# eeZeeAmp.net
KiCad netlist of a schematic drawn in EAGLE
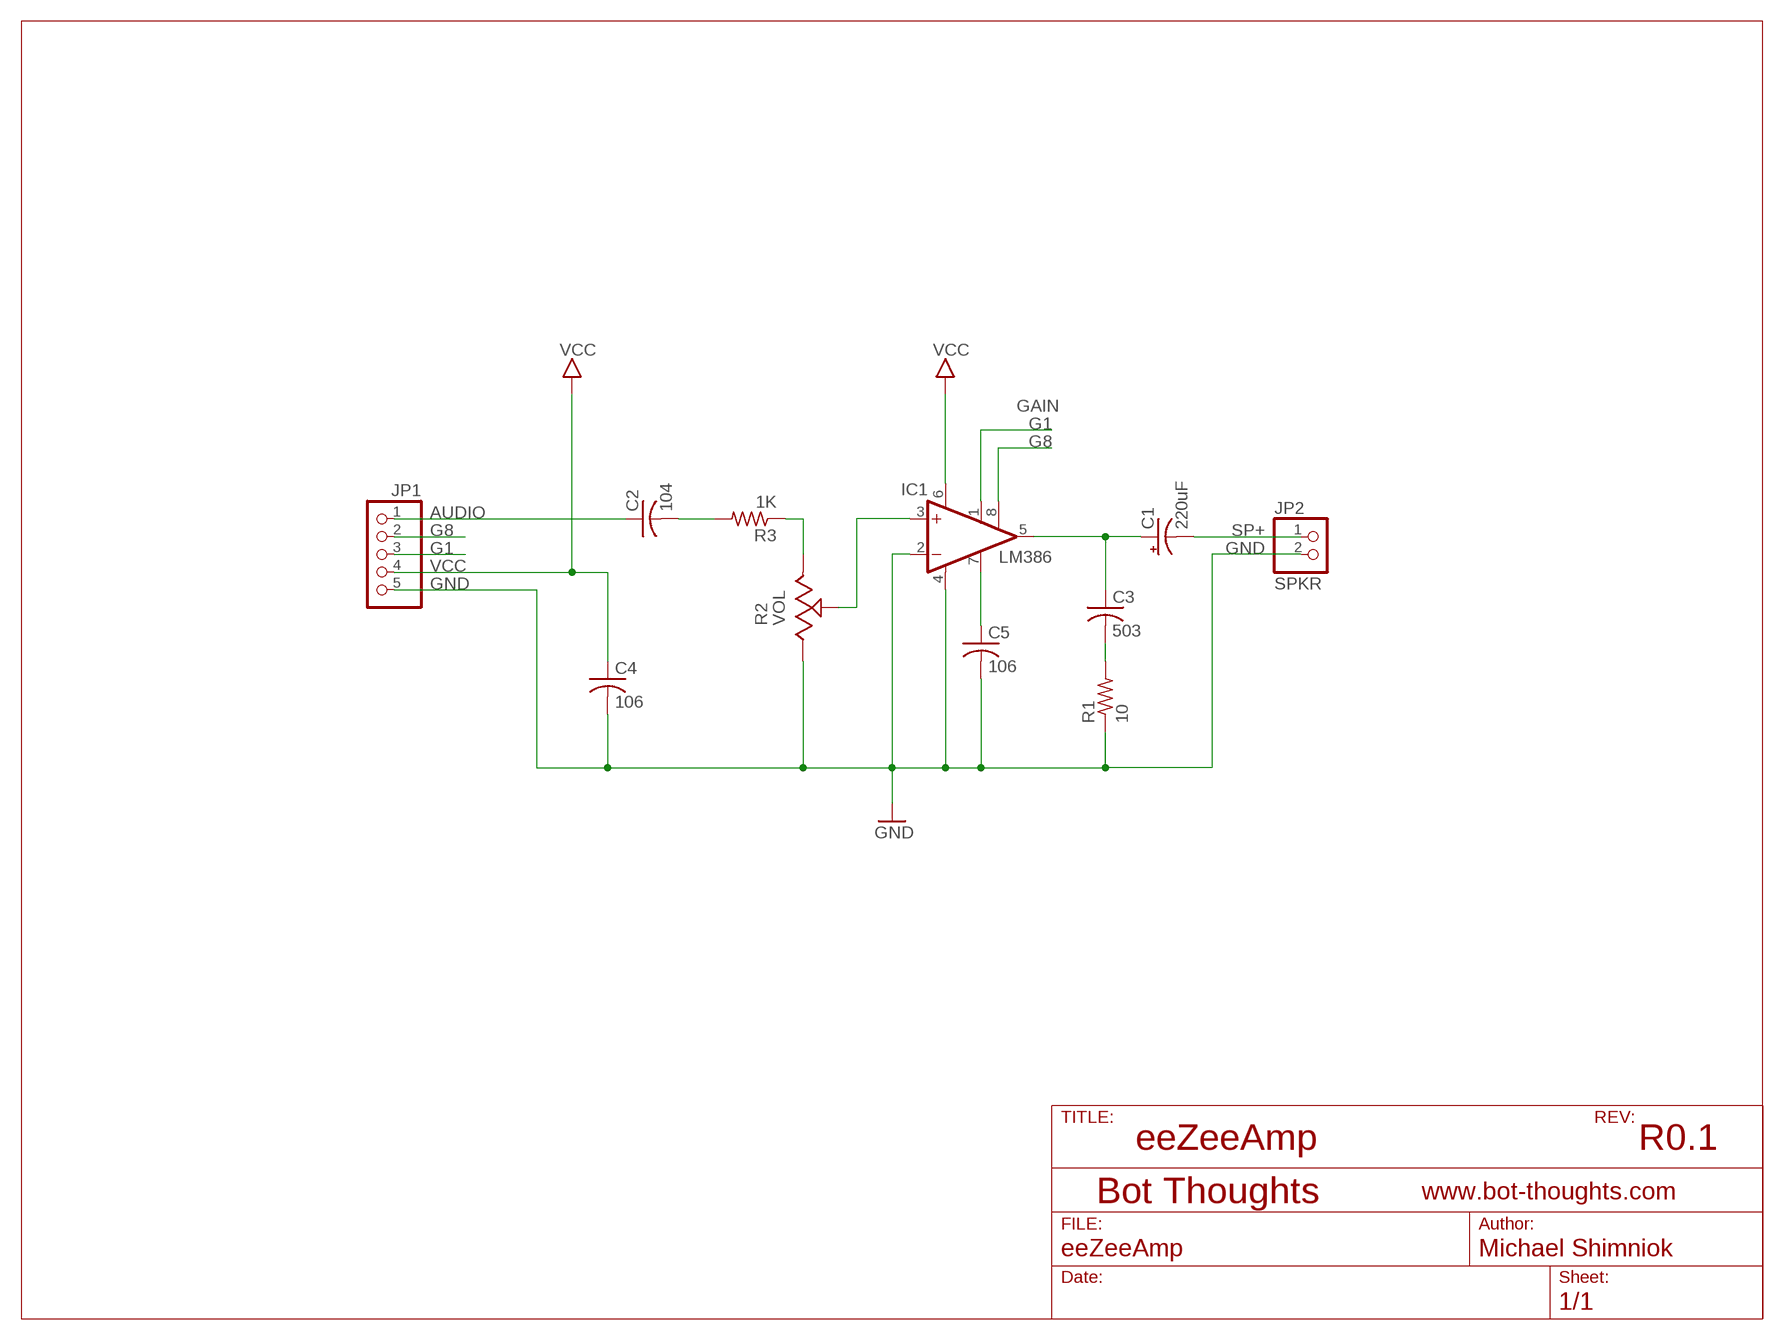
[diagram p0: schematic, sheet 1]

(export (version "E")
  (design (tool "Eeschema 10.0.6"))
  (components
    (comp (ref "C1")
      (value "220uF")
      (footprint "eagle-import:E2,5-6")
      (libsource (lib "eagle-import") (part "CPOL-USE2.5-6"))
    )
    (comp (ref "C2")
      (value "104")
      (footprint "eagle-import:C0603")
      (libsource (lib "eagle-import") (part "C-USC0603"))
    )
    (comp (ref "C3")
      (value "503")
      (footprint "eagle-import:C0603")
      (libsource (lib "eagle-import") (part "C-USC0603"))
    )
    (comp (ref "C4")
      (value "106")
      (footprint "eagle-import:C1206")
      (libsource (lib "eagle-import") (part "C-USC1206"))
    )
    (comp (ref "C5")
      (value "106")
      (footprint "eagle-import:C1206")
      (libsource (lib "eagle-import") (part "C-USC1206"))
    )
    (comp (ref "IC1")
      (value "LM386")
      (footprint "eagle-import:SO08")
      (libsource (lib "eagle-import") (part "LM386?-M1"))
    )
    (comp (ref "JP1")
      (value "PINHD-1X05_2.54-S")
      (footprint "eagle-import:1X05-S")
      (libsource (lib "eagle-import") (part "PINHD-1X05_2.54-S"))
    )
    (comp (ref "JP2")
      (value "SPKR")
      (footprint "eagle-import:1X02-S")
      (libsource (lib "eagle-import") (part "PINHD-1X02_2.54-S"))
    )
    (comp (ref "R1")
      (value "10")
      (footprint "eagle-import:R0603")
      (libsource (lib "eagle-import") (part "R-US_R0603"))
    )
    (comp (ref "R2")
      (value "VOL")
      (footprint "eagle-import:OFFBOARD_POT_3")
      (libsource (lib "eagle-import") (part "TRIM_US-"))
    )
    (comp (ref "R3")
      (value "1K")
      (footprint "eagle-import:R0603")
      (libsource (lib "eagle-import") (part "R-US_R0603"))
    )
  )
  (nets
    (net (code "1") (name "/AUDIO") (class "Default")
      (node (ref "C2") (pin "1") (pinfunction "1_1") (pintype "passive"))
      (node (ref "JP1") (pin "1") (pinfunction "1_1") (pintype "passive"))
    )
    (net (code "2") (name "/G1") (class "Default")
      (node (ref "IC1") (pin "1") (pinfunction "GAIN_1") (pintype "passive"))
      (node (ref "JP1") (pin "3") (pinfunction "3_3") (pintype "passive"))
    )
    (net (code "3") (name "/G8") (class "Default")
      (node (ref "IC1") (pin "8") (pinfunction "GAIN_8") (pintype "passive"))
      (node (ref "JP1") (pin "2") (pinfunction "2_2") (pintype "passive"))
    )
    (net (code "4") (name "/SP+") (class "Default")
      (node (ref "C1") (pin "-") (pinfunction "-_-") (pintype "passive"))
      (node (ref "JP2") (pin "1") (pinfunction "1_1") (pintype "passive"))
    )
    (net (code "5") (name "GND") (class "Default")
      (node (ref "C4") (pin "2") (pinfunction "2_2") (pintype "passive"))
      (node (ref "C5") (pin "2") (pinfunction "2_2") (pintype "passive"))
      (node (ref "IC1") (pin "2") (pinfunction "-IN_2") (pintype "input"))
      (node (ref "IC1") (pin "4") (pinfunction "GND_4") (pintype "power_in"))
      (node (ref "JP1") (pin "5") (pinfunction "5_5") (pintype "passive"))
      (node (ref "JP2") (pin "2") (pinfunction "2_2") (pintype "passive"))
      (node (ref "R1") (pin "1") (pinfunction "1_1") (pintype "passive"))
      (node (ref "R2") (pin "P$1") (pinfunction "A_P$1") (pintype "passive"))
    )
    (net (code "6") (name "Net-(C2-Pad2)") (class "Default")
      (node (ref "C2") (pin "2") (pinfunction "2_2") (pintype "passive"))
      (node (ref "R3") (pin "2") (pinfunction "2_2") (pintype "passive"))
    )
    (net (code "7") (name "Net-(C3-Pad2)") (class "Default")
      (node (ref "C3") (pin "2") (pinfunction "2_2") (pintype "passive"))
      (node (ref "R1") (pin "2") (pinfunction "2_2") (pintype "passive"))
    )
    (net (code "8") (name "Net-(IC1-+IN)") (class "Default")
      (node (ref "IC1") (pin "3") (pinfunction "+IN_3") (pintype "input"))
      (node (ref "R2") (pin "P$2") (pinfunction "S_P$2") (pintype "passive"))
    )
    (net (code "9") (name "Net-(IC1-BYPASS)") (class "Default")
      (node (ref "C5") (pin "1") (pinfunction "1_1") (pintype "passive"))
      (node (ref "IC1") (pin "7") (pinfunction "BYPASS_7") (pintype "passive"))
    )
    (net (code "10") (name "Net-(IC1-OUT)") (class "Default")
      (node (ref "C1") (pin "+") (pinfunction "+_+") (pintype "passive"))
      (node (ref "C3") (pin "1") (pinfunction "1_1") (pintype "passive"))
      (node (ref "IC1") (pin "5") (pinfunction "OUT_5") (pintype "output"))
    )
    (net (code "11") (name "Net-(R2-E)") (class "Default")
      (node (ref "R2") (pin "P$3") (pinfunction "E_P$3") (pintype "passive"))
      (node (ref "R3") (pin "1") (pinfunction "1_1") (pintype "passive"))
    )
    (net (code "12") (name "VCC") (class "Default")
      (node (ref "C4") (pin "1") (pinfunction "1_1") (pintype "passive"))
      (node (ref "IC1") (pin "6") (pinfunction "VS_6") (pintype "power_in"))
      (node (ref "JP1") (pin "4") (pinfunction "4_4") (pintype "passive"))
    )
  )
)
